# TP_IHM_CONNECTOR.net
KiCad netlist of a schematic drawn in Altium Designer
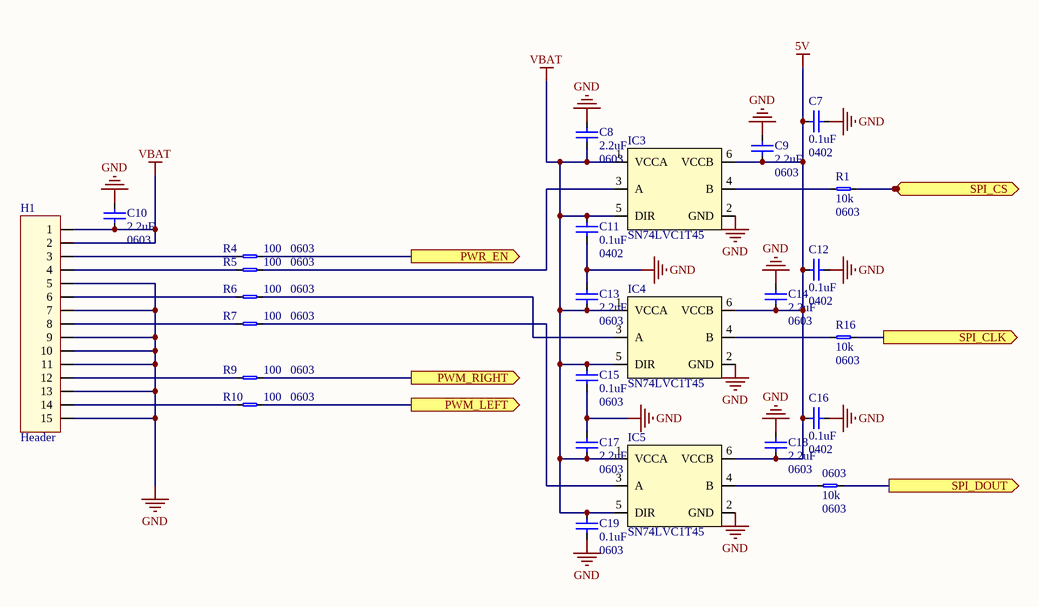
[diagram p0: TP_IHM_CONNECTOR.SchDoc]

(export (version "E")
  (design (tool "Eeschema 10.0.6"))
  (components
    (comp (ref "0603")
      (value "10k")
      (footprint "0603_RES_LD")
      (description "Resistor")
      (fields (field (name "PACKAGE") "0603"))
      (libsource (lib "TpGiven") (part "Resistor"))
    )
    (comp (ref "C7")
      (value "0.1uF")
      (footprint "0603_CAP_LD")
      (description "Ceramic Capacitor")
      (fields (field (name "PACKAGE") "0402") (field (name "Comment") "CerCap"))
      (libsource (lib "TpGiven") (part "CerCap"))
    )
    (comp (ref "C8")
      (value "2.2uF")
      (footprint "0603_CAP_LD")
      (description "Ceramic Capacitor")
      (fields (field (name "PACKAGE") "0603") (field (name "Comment") "CerCap"))
      (libsource (lib "TpGiven") (part "CerCap"))
    )
    (comp (ref "C9")
      (value "2.2uF")
      (footprint "0603_CAP_LD")
      (description "Ceramic Capacitor")
      (fields (field (name "PACKAGE") "0603") (field (name "Comment") "CerCap"))
      (libsource (lib "TpGiven") (part "CerCap"))
    )
    (comp (ref "C10")
      (value "2.2uF")
      (footprint "0603_CAP_LD")
      (description "Ceramic Capacitor")
      (fields (field (name "PACKAGE") "0603") (field (name "Comment") "CerCap"))
      (libsource (lib "TpGiven") (part "CerCap"))
    )
    (comp (ref "C11")
      (value "0.1uF")
      (footprint "0603_CAP_LD")
      (description "Ceramic Capacitor")
      (fields (field (name "PACKAGE") "0402") (field (name "Comment") "CerCap"))
      (libsource (lib "TpGiven") (part "CerCap"))
    )
    (comp (ref "C12")
      (value "0.1uF")
      (footprint "0603_CAP_LD")
      (description "Ceramic Capacitor")
      (fields (field (name "PACKAGE") "0402") (field (name "Comment") "CerCap"))
      (libsource (lib "TpGiven") (part "CerCap"))
    )
    (comp (ref "C13")
      (value "2.2uF")
      (footprint "0603_CAP_LD")
      (description "Ceramic Capacitor")
      (fields (field (name "PACKAGE") "0603") (field (name "Comment") "CerCap"))
      (libsource (lib "TpGiven") (part "CerCap"))
    )
    (comp (ref "C14")
      (value "2.2uF")
      (footprint "0603_CAP_LD")
      (description "Ceramic Capacitor")
      (fields (field (name "PACKAGE") "0603") (field (name "Comment") "CerCap"))
      (libsource (lib "TpGiven") (part "CerCap"))
    )
    (comp (ref "C15")
      (value "0.1uF")
      (footprint "0603_CAP_LD")
      (description "Ceramic Capacitor")
      (fields (field (name "PACKAGE") "0603") (field (name "Comment") "CerCap"))
      (libsource (lib "TpGiven") (part "CerCap"))
    )
    (comp (ref "C16")
      (value "0.1uF")
      (footprint "0603_CAP_LD")
      (description "Ceramic Capacitor")
      (fields (field (name "PACKAGE") "0402") (field (name "Comment") "CerCap"))
      (libsource (lib "TpGiven") (part "CerCap"))
    )
    (comp (ref "C17")
      (value "2.2uF")
      (footprint "0603_CAP_LD")
      (description "Ceramic Capacitor")
      (fields (field (name "PACKAGE") "0603") (field (name "Comment") "CerCap"))
      (libsource (lib "TpGiven") (part "CerCap"))
    )
    (comp (ref "C18")
      (value "2.2uF")
      (footprint "0603_CAP_LD")
      (description "Ceramic Capacitor")
      (fields (field (name "PACKAGE") "0603") (field (name "Comment") "CerCap"))
      (libsource (lib "TpGiven") (part "CerCap"))
    )
    (comp (ref "C19")
      (value "0.1uF")
      (footprint "0603_CAP_LD")
      (description "Ceramic Capacitor")
      (fields (field (name "PACKAGE") "0603") (field (name "Comment") "CerCap"))
      (libsource (lib "TpGiven") (part "CerCap"))
    )
    (comp (ref "H1")
      (value "Header")
      (footprint "653115131822")
      (description "Header 15x1")
      (libsource (lib "TpGiven") (part "HEADER_15x1"))
    )
    (comp (ref "IC3")
      (value "SN74LVC1T45")
      (footprint "MO-203AB_LD")
      (description "Single Bit Dual Supply Buffer")
      (libsource (lib "TpGiven") (part "SN74LVC1T45"))
    )
    (comp (ref "IC4")
      (value "SN74LVC1T45")
      (footprint "MO-203AB_LD")
      (description "Single Bit Dual Supply Buffer")
      (libsource (lib "TpGiven") (part "SN74LVC1T45"))
    )
    (comp (ref "IC5")
      (value "SN74LVC1T45")
      (footprint "MO-203AB_LD")
      (description "Single Bit Dual Supply Buffer")
      (libsource (lib "TpGiven") (part "SN74LVC1T45"))
    )
    (comp (ref "R1")
      (value "10k")
      (footprint "0603_RES_LD")
      (description "Resistor")
      (fields (field (name "PACKAGE") "0603"))
      (libsource (lib "TpGiven") (part "Resistor"))
    )
    (comp (ref "R4")
      (value "100")
      (footprint "0603_RES_LD")
      (description "Resistor")
      (fields (field (name "PACKAGE") "0603"))
      (libsource (lib "TpGiven") (part "Resistor"))
    )
    (comp (ref "R5")
      (value "100")
      (footprint "0603_RES_LD")
      (description "Resistor")
      (fields (field (name "PACKAGE") "0603"))
      (libsource (lib "TpGiven") (part "Resistor"))
    )
    (comp (ref "R6")
      (value "100")
      (footprint "0603_RES_LD")
      (description "Resistor")
      (fields (field (name "PACKAGE") "0603"))
      (libsource (lib "TpGiven") (part "Resistor"))
    )
    (comp (ref "R7")
      (value "100")
      (footprint "0603_RES_LD")
      (description "Resistor")
      (fields (field (name "PACKAGE") "0603"))
      (libsource (lib "TpGiven") (part "Resistor"))
    )
    (comp (ref "R9")
      (value "100")
      (footprint "0603_RES_LD")
      (description "Resistor")
      (fields (field (name "PACKAGE") "0603"))
      (libsource (lib "TpGiven") (part "Resistor"))
    )
    (comp (ref "R10")
      (value "100")
      (footprint "0603_RES_LD")
      (description "Resistor")
      (fields (field (name "PACKAGE") "0603"))
      (libsource (lib "TpGiven") (part "Resistor"))
    )
    (comp (ref "R16")
      (value "10k")
      (footprint "0603_RES_LD")
      (description "Resistor")
      (fields (field (name "PACKAGE") "0603"))
      (libsource (lib "TpGiven") (part "Resistor"))
    )
  )
  (nets
    (net (code "1") (name "/PWM_LEFT") (class "Default")
      (node (ref "R10") (pin "2") (pinfunction "2_2") (pintype "passive"))
    )
    (net (code "2") (name "/PWM_RIGHT") (class "Default")
      (node (ref "R9") (pin "2") (pinfunction "2_2") (pintype "passive"))
    )
    (net (code "3") (name "/PWR_EN") (class "Default")
      (node (ref "R4") (pin "2") (pinfunction "2_2") (pintype "passive"))
    )
    (net (code "4") (name "/SPI_CLK") (class "Default")
      (node (ref "R16") (pin "2") (pinfunction "2_2") (pintype "passive"))
    )
    (net (code "5") (name "/SPI_CS") (class "Default")
      (node (ref "R1") (pin "2") (pinfunction "2_2") (pintype "passive"))
    )
    (net (code "6") (name "/SPI_DOUT") (class "Default")
      (node (ref "0603") (pin "2") (pinfunction "2_2") (pintype "passive"))
    )
    (net (code "7") (name "5V") (class "Default")
      (node (ref "C12") (pin "2") (pinfunction "2_2") (pintype "passive"))
      (node (ref "C14") (pin "1") (pinfunction "1_1") (pintype "passive"))
      (node (ref "C16") (pin "2") (pinfunction "2_2") (pintype "passive"))
      (node (ref "C18") (pin "1") (pinfunction "1_1") (pintype "passive"))
      (node (ref "C7") (pin "2") (pinfunction "2_2") (pintype "passive"))
      (node (ref "C9") (pin "1") (pinfunction "1_1") (pintype "passive"))
      (node (ref "IC3") (pin "6") (pinfunction "VCCB_6") (pintype "passive"))
      (node (ref "IC4") (pin "6") (pinfunction "VCCB_6") (pintype "passive"))
      (node (ref "IC5") (pin "6") (pinfunction "VCCB_6") (pintype "passive"))
    )
    (net (code "8") (name "GND") (class "Default")
      (node (ref "C10") (pin "2") (pinfunction "2_2") (pintype "passive"))
      (node (ref "C11") (pin "1") (pinfunction "1_1") (pintype "passive"))
      (node (ref "C12") (pin "1") (pinfunction "1_1") (pintype "passive"))
      (node (ref "C13") (pin "2") (pinfunction "2_2") (pintype "passive"))
      (node (ref "C14") (pin "2") (pinfunction "2_2") (pintype "passive"))
      (node (ref "C15") (pin "1") (pinfunction "1_1") (pintype "passive"))
      (node (ref "C16") (pin "1") (pinfunction "1_1") (pintype "passive"))
      (node (ref "C17") (pin "2") (pinfunction "2_2") (pintype "passive"))
      (node (ref "C18") (pin "2") (pinfunction "2_2") (pintype "passive"))
      (node (ref "C19") (pin "1") (pinfunction "1_1") (pintype "passive"))
      (node (ref "C7") (pin "1") (pinfunction "1_1") (pintype "passive"))
      (node (ref "C8") (pin "2") (pinfunction "2_2") (pintype "passive"))
      (node (ref "C9") (pin "2") (pinfunction "2_2") (pintype "passive"))
      (node (ref "H1") (pin "10") (pinfunction "10_10") (pintype "passive"))
      (node (ref "H1") (pin "11") (pinfunction "11_11") (pintype "passive"))
      (node (ref "H1") (pin "13") (pinfunction "13_13") (pintype "passive"))
      (node (ref "H1") (pin "15") (pinfunction "15_15") (pintype "passive"))
      (node (ref "H1") (pin "5") (pinfunction "5_5") (pintype "passive"))
      (node (ref "H1") (pin "7") (pinfunction "7_7") (pintype "passive"))
      (node (ref "H1") (pin "9") (pinfunction "9_9") (pintype "passive"))
      (node (ref "IC3") (pin "2") (pinfunction "GND_2") (pintype "passive"))
      (node (ref "IC4") (pin "2") (pinfunction "GND_2") (pintype "passive"))
      (node (ref "IC5") (pin "2") (pinfunction "GND_2") (pintype "passive"))
    )
    (net (code "9") (name "Net-(H1-Pad3)") (class "Default")
      (node (ref "H1") (pin "3") (pinfunction "3_3") (pintype "passive"))
      (node (ref "R4") (pin "1") (pinfunction "1_1") (pintype "passive"))
    )
    (net (code "10") (name "Net-(H1-Pad4)") (class "Default")
      (node (ref "H1") (pin "4") (pinfunction "4_4") (pintype "passive"))
      (node (ref "R5") (pin "1") (pinfunction "1_1") (pintype "passive"))
    )
    (net (code "11") (name "Net-(H1-Pad6)") (class "Default")
      (node (ref "H1") (pin "6") (pinfunction "6_6") (pintype "passive"))
      (node (ref "R6") (pin "1") (pinfunction "1_1") (pintype "passive"))
    )
    (net (code "12") (name "Net-(H1-Pad8)") (class "Default")
      (node (ref "H1") (pin "8") (pinfunction "8_8") (pintype "passive"))
      (node (ref "R7") (pin "1") (pinfunction "1_1") (pintype "passive"))
    )
    (net (code "13") (name "Net-(H1-Pad12)") (class "Default")
      (node (ref "H1") (pin "12") (pinfunction "12_12") (pintype "passive"))
      (node (ref "R9") (pin "1") (pinfunction "1_1") (pintype "passive"))
    )
    (net (code "14") (name "Net-(H1-Pad14)") (class "Default")
      (node (ref "H1") (pin "14") (pinfunction "14_14") (pintype "passive"))
      (node (ref "R10") (pin "1") (pinfunction "1_1") (pintype "passive"))
    )
    (net (code "15") (name "Net-(IC3-A)") (class "Default")
      (node (ref "IC3") (pin "3") (pinfunction "A_3") (pintype "passive"))
      (node (ref "R5") (pin "2") (pinfunction "2_2") (pintype "passive"))
    )
    (net (code "16") (name "Net-(IC3-B)") (class "Default")
      (node (ref "IC3") (pin "4") (pinfunction "B_4") (pintype "passive"))
      (node (ref "R1") (pin "1") (pinfunction "1_1") (pintype "passive"))
    )
    (net (code "17") (name "Net-(IC4-A)") (class "Default")
      (node (ref "IC4") (pin "3") (pinfunction "A_3") (pintype "passive"))
      (node (ref "R6") (pin "2") (pinfunction "2_2") (pintype "passive"))
    )
    (net (code "18") (name "Net-(IC4-B)") (class "Default")
      (node (ref "IC4") (pin "4") (pinfunction "B_4") (pintype "passive"))
      (node (ref "R16") (pin "1") (pinfunction "1_1") (pintype "passive"))
    )
    (net (code "19") (name "Net-(IC5-A)") (class "Default")
      (node (ref "IC5") (pin "3") (pinfunction "A_3") (pintype "passive"))
      (node (ref "R7") (pin "2") (pinfunction "2_2") (pintype "passive"))
    )
    (net (code "20") (name "Net-(IC5-B)") (class "Default")
      (node (ref "0603") (pin "1") (pinfunction "1_1") (pintype "passive"))
      (node (ref "IC5") (pin "4") (pinfunction "B_4") (pintype "passive"))
    )
    (net (code "21") (name "VBAT") (class "Default")
      (node (ref "C10") (pin "1") (pinfunction "1_1") (pintype "passive"))
      (node (ref "C11") (pin "2") (pinfunction "2_2") (pintype "passive"))
      (node (ref "C13") (pin "1") (pinfunction "1_1") (pintype "passive"))
      (node (ref "C15") (pin "2") (pinfunction "2_2") (pintype "passive"))
      (node (ref "C17") (pin "1") (pinfunction "1_1") (pintype "passive"))
      (node (ref "C19") (pin "2") (pinfunction "2_2") (pintype "passive"))
      (node (ref "C8") (pin "1") (pinfunction "1_1") (pintype "passive"))
      (node (ref "H1") (pin "1") (pinfunction "1_1") (pintype "passive"))
      (node (ref "H1") (pin "2") (pinfunction "2_2") (pintype "passive"))
      (node (ref "IC3") (pin "1") (pinfunction "VCCA_1") (pintype "passive"))
      (node (ref "IC3") (pin "5") (pinfunction "DIR_5") (pintype "passive"))
      (node (ref "IC4") (pin "1") (pinfunction "VCCA_1") (pintype "passive"))
      (node (ref "IC4") (pin "5") (pinfunction "DIR_5") (pintype "passive"))
      (node (ref "IC5") (pin "1") (pinfunction "VCCA_1") (pintype "passive"))
      (node (ref "IC5") (pin "5") (pinfunction "DIR_5") (pintype "passive"))
    )
  )
)
